# 2022-4T-MNT-1.net
KiCad netlist of a schematic drawn in EasyEDA Pro
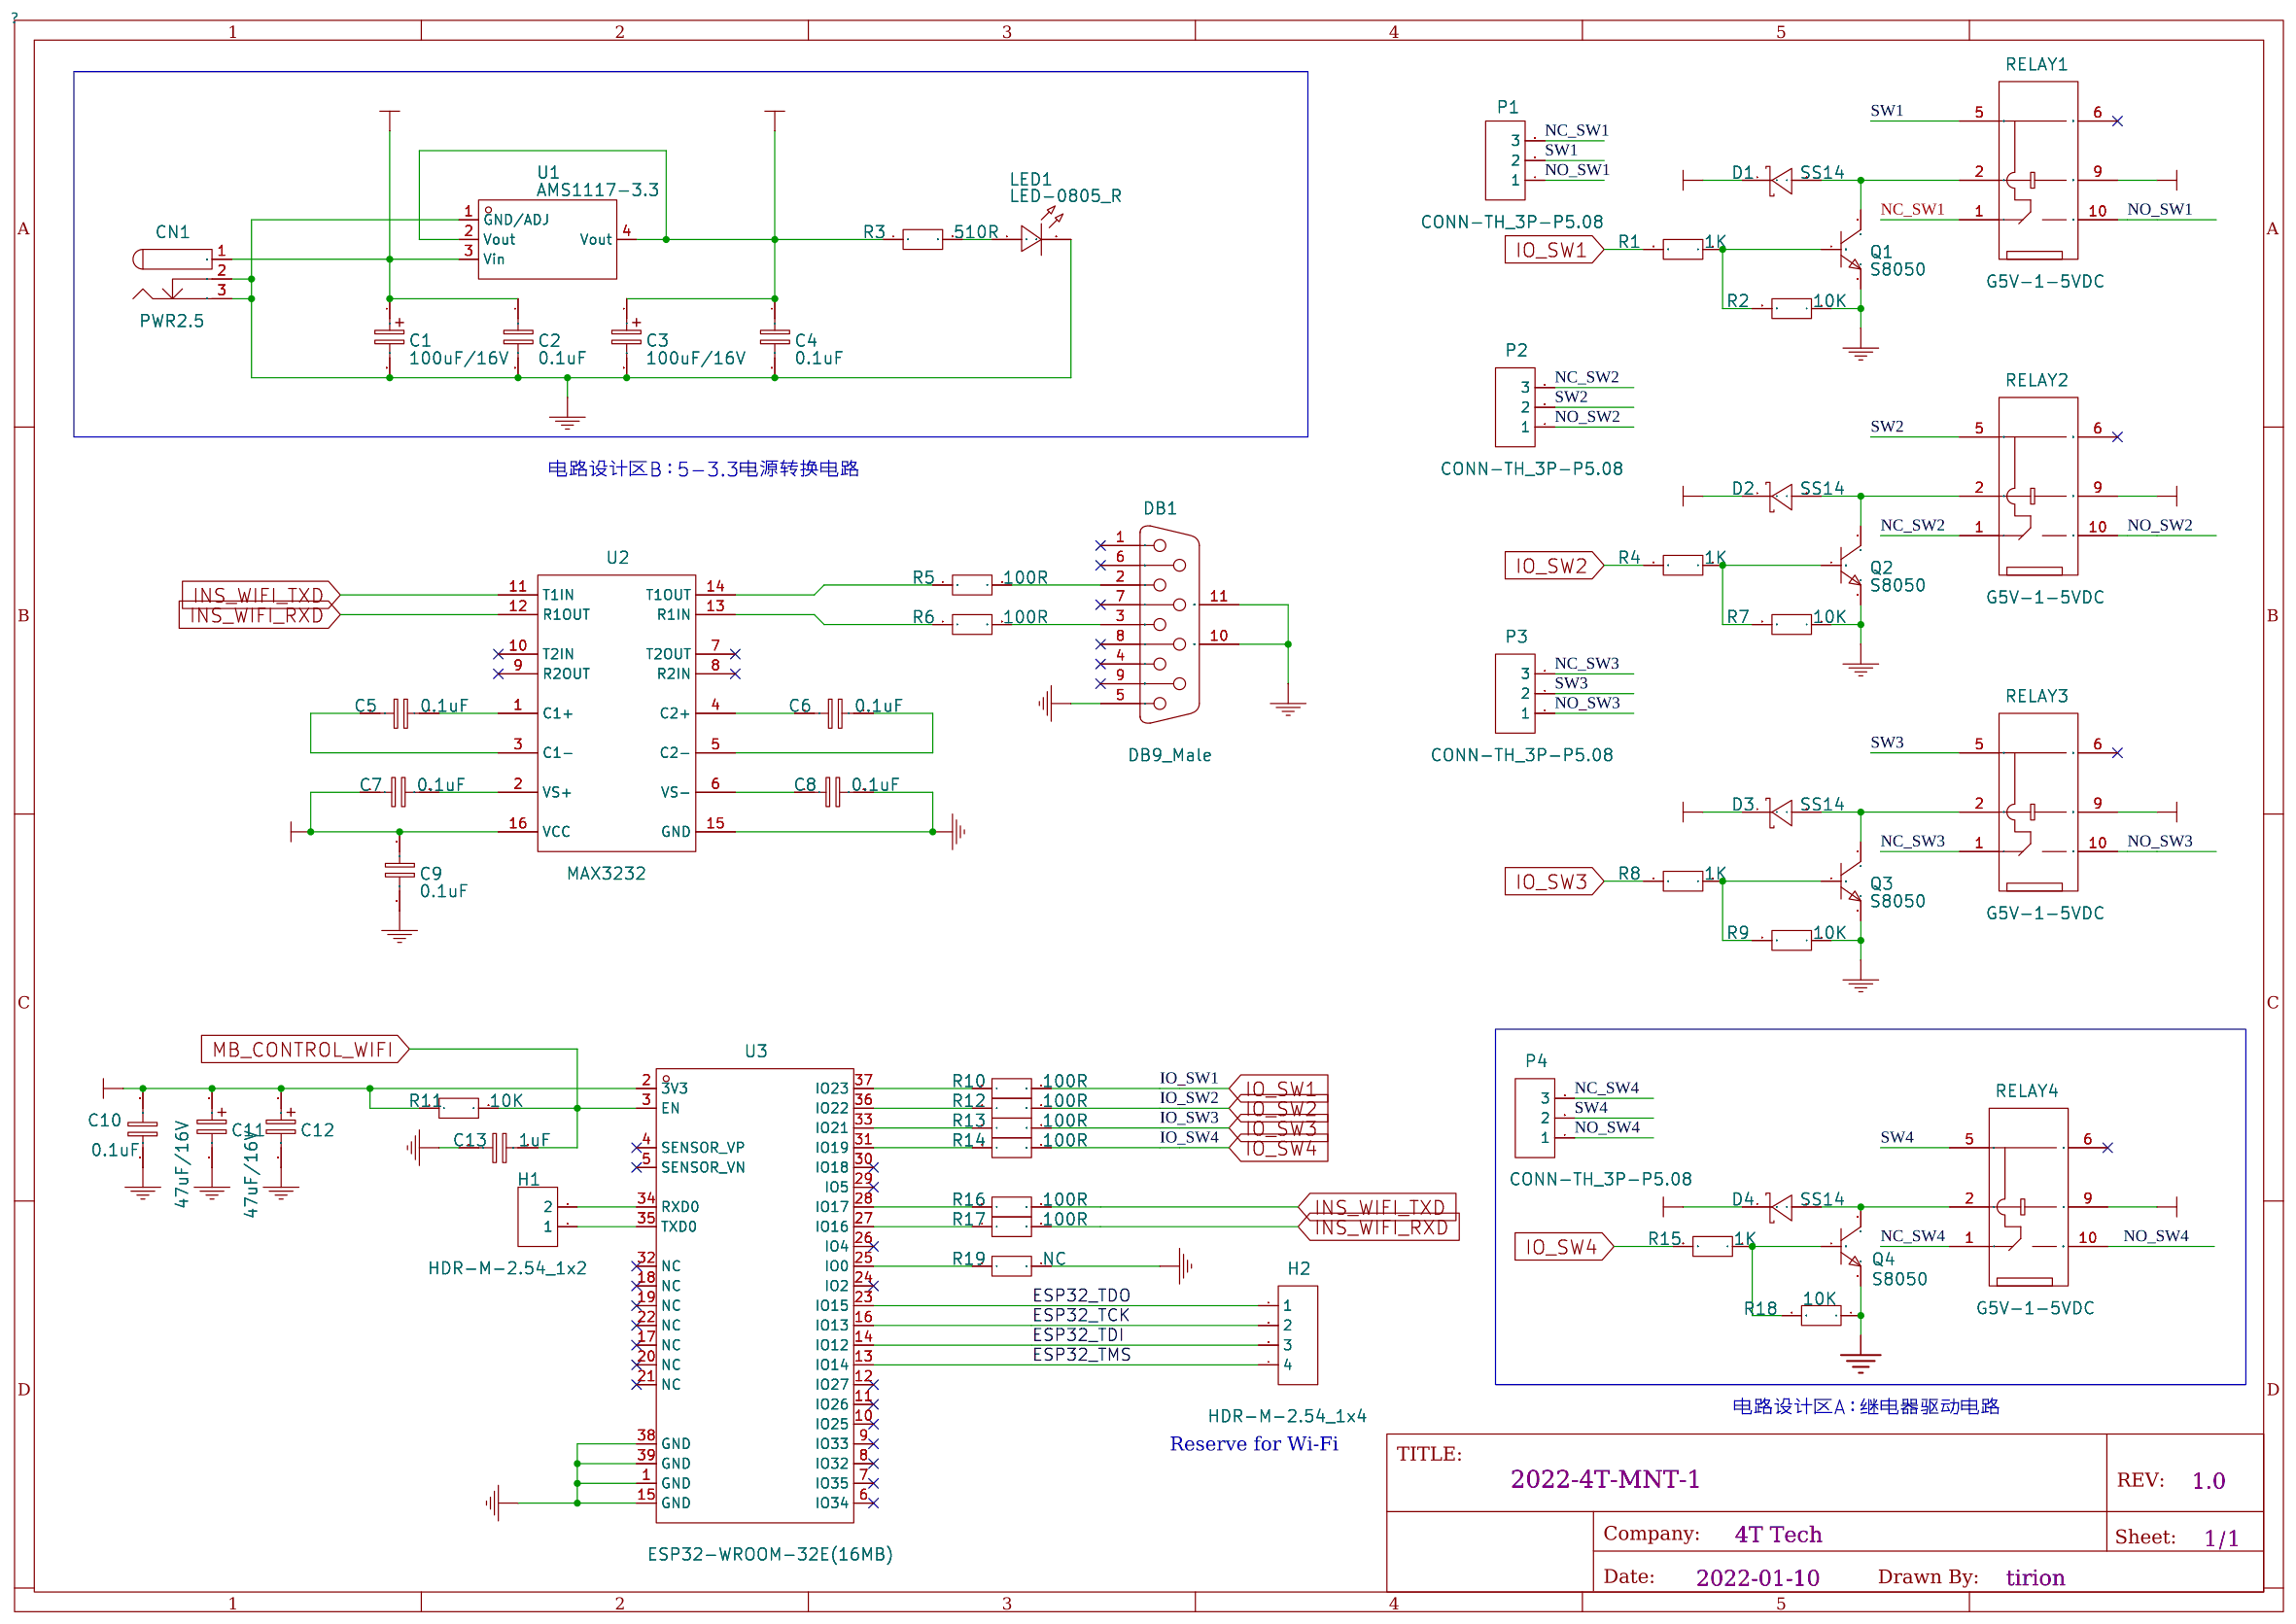
[diagram p0: schematic sheet]

(export (version "E")
  (design (tool "Eeschema 10.0.6"))
  (components
    (comp (ref "C1") (value "100uF/16V") (libsource (lib "easyedapro") (part "100uF/16V")))
    (comp (ref "C2") (value "0.1uF") (libsource (lib "easyedapro") (part "0.1uF")))
    (comp (ref "C3") (value "100uF/16V") (libsource (lib "easyedapro") (part "100uF/16V")))
    (comp (ref "C4") (value "0.1uF") (libsource (lib "easyedapro") (part "0.1uF")))
    (comp (ref "C5") (value "0.1uF") (libsource (lib "easyedapro") (part "0.1uF")))
    (comp (ref "C6") (value "0.1uF") (libsource (lib "easyedapro") (part "0.1uF")))
    (comp (ref "C7") (value "0.1uF") (libsource (lib "easyedapro") (part "0.1uF")))
    (comp (ref "C8") (value "0.1uF") (libsource (lib "easyedapro") (part "0.1uF")))
    (comp (ref "C9") (value "0.1uF") (libsource (lib "easyedapro") (part "0.1uF")))
    (comp (ref "C10") (value "0.1uF") (libsource (lib "easyedapro") (part "0.1uF")))
    (comp (ref "C11") (value "47uF/16V") (libsource (lib "easyedapro") (part "47uF/16V")))
    (comp (ref "C12") (value "47uF/16V") (libsource (lib "easyedapro") (part "47uF/16V")))
    (comp (ref "C13") (value "1uF") (libsource (lib "easyedapro") (part "1uF")))
    (comp (ref "CN1") (value "PWR2.5") (libsource (lib "easyedapro") (part "PWR2.5")))
    (comp (ref "D1")
      (value "SS14")
      (fields (field (name "Manufacturer") "MDD"))
      (libsource (lib "easyedapro") (part "SS14"))
    )
    (comp (ref "D2")
      (value "SS14")
      (fields (field (name "Manufacturer") "MDD"))
      (libsource (lib "easyedapro") (part "SS14"))
    )
    (comp (ref "D3")
      (value "SS14")
      (fields (field (name "Manufacturer") "MDD"))
      (libsource (lib "easyedapro") (part "SS14"))
    )
    (comp (ref "D4")
      (value "SS14")
      (fields (field (name "Manufacturer") "MDD"))
      (libsource (lib "easyedapro") (part "SS14"))
    )
    (comp (ref "DB1")
      (value "DB9_Male")
      (fields (field (name "Manufacturer") "Amphenol"))
      (libsource (lib "easyedapro") (part "DB9_Male"))
    )
    (comp (ref "H1") (value "HDR-M-2.54_1x2") (libsource (lib "easyedapro") (part "HDR-M-2.54_1x2")))
    (comp (ref "H2") (value "HDR-M-2.54_1x4") (libsource (lib "easyedapro") (part "HDR-M-2.54_1x4")))
    (comp (ref "LED1")
      (value "LED-0805_R")
      (fields
        (field (name "Manufacturer Part") "17-21SURC/S530-A3/TR8")
        (field (name "Manufacturer") "EVERLIGHT(台湾亿光)")
      )
      (libsource (lib "easyedapro") (part "LED-0805_R"))
    )
    (comp (ref "P1") (value "CONN-TH_3P-P5.08") (libsource (lib "easyedapro") (part "CONN-TH_3P-P5.08")))
    (comp (ref "P2") (value "CONN-TH_3P-P5.08") (libsource (lib "easyedapro") (part "CONN-TH_3P-P5.08")))
    (comp (ref "P3") (value "CONN-TH_3P-P5.08") (libsource (lib "easyedapro") (part "CONN-TH_3P-P5.08")))
    (comp (ref "P4") (value "CONN-TH_3P-P5.08") (libsource (lib "easyedapro") (part "CONN-TH_3P-P5.08")))
    (comp (ref "Q1")
      (value "S8050")
      (fields (field (name "Manufacturer") "JSMSEMI"))
      (libsource (lib "easyedapro") (part "S8050"))
    )
    (comp (ref "Q2")
      (value "S8050")
      (fields (field (name "Manufacturer") "JSMSEMI"))
      (libsource (lib "easyedapro") (part "S8050"))
    )
    (comp (ref "Q3")
      (value "S8050")
      (fields (field (name "Manufacturer") "JSMSEMI"))
      (libsource (lib "easyedapro") (part "S8050"))
    )
    (comp (ref "Q4")
      (value "S8050")
      (fields (field (name "Manufacturer") "JSMSEMI"))
      (libsource (lib "easyedapro") (part "S8050"))
    )
    (comp (ref "R1") (value "1K") (libsource (lib "easyedapro") (part "1K")))
    (comp (ref "R2") (value "10K") (libsource (lib "easyedapro") (part "10K")))
    (comp (ref "R3") (value "510R") (libsource (lib "easyedapro") (part "510R")))
    (comp (ref "R4") (value "1K") (libsource (lib "easyedapro") (part "1K")))
    (comp (ref "R5") (value "100R") (libsource (lib "easyedapro") (part "100R")))
    (comp (ref "R6") (value "100R") (libsource (lib "easyedapro") (part "100R")))
    (comp (ref "R7") (value "10K") (libsource (lib "easyedapro") (part "10K")))
    (comp (ref "R8") (value "1K") (libsource (lib "easyedapro") (part "1K")))
    (comp (ref "R9") (value "10K") (libsource (lib "easyedapro") (part "10K")))
    (comp (ref "R10") (value "100R") (libsource (lib "easyedapro") (part "100R")))
    (comp (ref "R11") (value "10K") (libsource (lib "easyedapro") (part "10K")))
    (comp (ref "R12") (value "100R") (libsource (lib "easyedapro") (part "100R")))
    (comp (ref "R13") (value "100R") (libsource (lib "easyedapro") (part "100R")))
    (comp (ref "R14") (value "100R") (libsource (lib "easyedapro") (part "100R")))
    (comp (ref "R15") (value "1K") (libsource (lib "easyedapro") (part "1K")))
    (comp (ref "R16") (value "100R") (libsource (lib "easyedapro") (part "100R")))
    (comp (ref "R17") (value "100R") (libsource (lib "easyedapro") (part "100R")))
    (comp (ref "R18") (value "10K") (libsource (lib "easyedapro") (part "10K")))
    (comp (ref "R19") (value "NC") (libsource (lib "easyedapro") (part "NC")))
    (comp (ref "RELAY1")
      (value "G5V-1-5VDC")
      (fields (field (name "Manufacturer") "OMRON"))
      (libsource (lib "easyedapro") (part "G5V-1-5VDC"))
    )
    (comp (ref "RELAY2")
      (value "G5V-1-5VDC")
      (fields (field (name "Manufacturer") "OMRON"))
      (libsource (lib "easyedapro") (part "G5V-1-5VDC"))
    )
    (comp (ref "RELAY3")
      (value "G5V-1-5VDC")
      (fields (field (name "Manufacturer") "OMRON"))
      (libsource (lib "easyedapro") (part "G5V-1-5VDC"))
    )
    (comp (ref "RELAY4")
      (value "G5V-1-5VDC")
      (fields (field (name "Manufacturer") "OMRON"))
      (libsource (lib "easyedapro") (part "G5V-1-5VDC"))
    )
    (comp (ref "U1")
      (value "AMS1117-3.3")
      (fields (field (name "Manufacturer") "AMS"))
      (libsource (lib "easyedapro") (part "AMS1117-3.3"))
    )
    (comp (ref "U2")
      (value "MAX3232")
      (fields (field (name "Manufacturer") "TI"))
      (libsource (lib "easyedapro") (part "MAX3232"))
    )
    (comp (ref "U3")
      (value "ESP32-WROOM-32E(16MB)")
      (fields (field (name "Manufacturer") "Espressif Systems"))
      (libsource (lib "easyedapro") (part "ESP32-WROOM-32E(16MB)"))
    )
  )
  (nets
    (net (code "1") (name "+3V3") (class "Default")
      (node (ref "C10") (pin "2") (pinfunction "2_2") (pintype "input"))
      (node (ref "C11") (pin "1") (pinfunction "1_1") (pintype "input"))
      (node (ref "C12") (pin "1") (pinfunction "1_1") (pintype "input"))
      (node (ref "C3") (pin "1") (pinfunction "1_1") (pintype "input"))
      (node (ref "C4") (pin "1") (pinfunction "1_1") (pintype "input"))
      (node (ref "C7") (pin "1") (pinfunction "1_1") (pintype "input"))
      (node (ref "C9") (pin "1") (pinfunction "1_1") (pintype "input"))
      (node (ref "R11") (pin "1") (pinfunction "1_1") (pintype "input"))
      (node (ref "R3") (pin "1") (pinfunction "1_1") (pintype "input"))
      (node (ref "U1") (pin "2") (pinfunction "Vout_2") (pintype "input"))
      (node (ref "U1") (pin "4") (pinfunction "Vout_4") (pintype "input"))
      (node (ref "U2") (pin "16") (pinfunction "VCC_16") (pintype "input"))
      (node (ref "U3") (pin "2") (pinfunction "3V3_2") (pintype "input"))
    )
    (net (code "2") (name "+5V") (class "Default")
      (node (ref "C1") (pin "1") (pinfunction "1_1") (pintype "input"))
      (node (ref "C2") (pin "1") (pinfunction "1_1") (pintype "input"))
      (node (ref "CN1") (pin "1") (pinfunction "ADJ_1") (pintype "input"))
      (node (ref "D1") (pin "1") (pinfunction "K_1") (pintype "input"))
      (node (ref "D2") (pin "1") (pinfunction "K_1") (pintype "input"))
      (node (ref "D3") (pin "1") (pinfunction "K_1") (pintype "input"))
      (node (ref "D4") (pin "1") (pinfunction "K_1") (pintype "input"))
      (node (ref "RELAY1") (pin "9") (pinfunction "9_9") (pintype "input"))
      (node (ref "RELAY2") (pin "9") (pinfunction "9_9") (pintype "input"))
      (node (ref "RELAY3") (pin "9") (pinfunction "9_9") (pintype "input"))
      (node (ref "RELAY4") (pin "9") (pinfunction "9_9") (pintype "input"))
      (node (ref "U1") (pin "3") (pinfunction "Vin_3") (pintype "input"))
    )
    (net (code "3") (name "/ESP32_TCK") (class "Default")
      (node (ref "H2") (pin "2") (pinfunction "2_2") (pintype "input"))
      (node (ref "U3") (pin "16") (pinfunction "IO13_16") (pintype "input"))
    )
    (net (code "4") (name "/ESP32_TDI") (class "Default")
      (node (ref "H2") (pin "3") (pinfunction "3_3") (pintype "input"))
      (node (ref "U3") (pin "14") (pinfunction "IO12_14") (pintype "input"))
    )
    (net (code "5") (name "/ESP32_TDO") (class "Default")
      (node (ref "H2") (pin "1") (pinfunction "1_1") (pintype "input"))
      (node (ref "U3") (pin "23") (pinfunction "IO15_23") (pintype "input"))
    )
    (net (code "6") (name "/ESP32_TMS") (class "Default")
      (node (ref "H2") (pin "4") (pinfunction "4_4") (pintype "input"))
      (node (ref "U3") (pin "13") (pinfunction "IO14_13") (pintype "input"))
    )
    (net (code "7") (name "/NC_SW1") (class "Default")
      (node (ref "P1") (pin "3") (pinfunction "3_3") (pintype "input"))
      (node (ref "RELAY1") (pin "1") (pinfunction "1_1") (pintype "input"))
    )
    (net (code "8") (name "/NC_SW2") (class "Default")
      (node (ref "P2") (pin "3") (pinfunction "3_3") (pintype "input"))
      (node (ref "RELAY2") (pin "1") (pinfunction "1_1") (pintype "input"))
    )
    (net (code "9") (name "/NC_SW3") (class "Default")
      (node (ref "P3") (pin "3") (pinfunction "3_3") (pintype "input"))
      (node (ref "RELAY3") (pin "1") (pinfunction "1_1") (pintype "input"))
    )
    (net (code "10") (name "/NC_SW4") (class "Default")
      (node (ref "P4") (pin "3") (pinfunction "3_3") (pintype "input"))
      (node (ref "RELAY4") (pin "1") (pinfunction "1_1") (pintype "input"))
    )
    (net (code "11") (name "/NO_SW1") (class "Default")
      (node (ref "P1") (pin "1") (pinfunction "1_1") (pintype "input"))
      (node (ref "RELAY1") (pin "10") (pinfunction "10_10") (pintype "input"))
    )
    (net (code "12") (name "/NO_SW2") (class "Default")
      (node (ref "P2") (pin "1") (pinfunction "1_1") (pintype "input"))
      (node (ref "RELAY2") (pin "10") (pinfunction "10_10") (pintype "input"))
    )
    (net (code "13") (name "/NO_SW3") (class "Default")
      (node (ref "P3") (pin "1") (pinfunction "1_1") (pintype "input"))
      (node (ref "RELAY3") (pin "10") (pinfunction "10_10") (pintype "input"))
    )
    (net (code "14") (name "/NO_SW4") (class "Default")
      (node (ref "P4") (pin "1") (pinfunction "1_1") (pintype "input"))
      (node (ref "RELAY4") (pin "10") (pinfunction "10_10") (pintype "input"))
    )
    (net (code "15") (name "/SW1") (class "Default")
      (node (ref "P1") (pin "2") (pinfunction "2_2") (pintype "input"))
      (node (ref "RELAY1") (pin "5") (pinfunction "5_5") (pintype "input"))
    )
    (net (code "16") (name "/SW2") (class "Default")
      (node (ref "P2") (pin "2") (pinfunction "2_2") (pintype "input"))
      (node (ref "RELAY2") (pin "5") (pinfunction "5_5") (pintype "input"))
    )
    (net (code "17") (name "/SW3") (class "Default")
      (node (ref "P3") (pin "2") (pinfunction "2_2") (pintype "input"))
      (node (ref "RELAY3") (pin "5") (pinfunction "5_5") (pintype "input"))
    )
    (net (code "18") (name "/SW4") (class "Default")
      (node (ref "P4") (pin "2") (pinfunction "2_2") (pintype "input"))
      (node (ref "RELAY4") (pin "5") (pinfunction "5_5") (pintype "input"))
    )
    (net (code "19") (name "GND") (class "Default")
      (node (ref "C1") (pin "2") (pinfunction "2_2") (pintype "input"))
      (node (ref "C10") (pin "1") (pinfunction "1_1") (pintype "input"))
      (node (ref "C11") (pin "2") (pinfunction "2_2") (pintype "input"))
      (node (ref "C12") (pin "2") (pinfunction "2_2") (pintype "input"))
      (node (ref "C13") (pin "2") (pinfunction "2_2") (pintype "input"))
      (node (ref "C2") (pin "2") (pinfunction "2_2") (pintype "input"))
      (node (ref "C3") (pin "2") (pinfunction "2_2") (pintype "input"))
      (node (ref "C4") (pin "2") (pinfunction "2_2") (pintype "input"))
      (node (ref "C8") (pin "2") (pinfunction "2_2") (pintype "input"))
      (node (ref "C9") (pin "2") (pinfunction "2_2") (pintype "input"))
      (node (ref "CN1") (pin "2") (pinfunction "ADJ_2") (pintype "input"))
      (node (ref "CN1") (pin "3") (pinfunction "ADJ_3") (pintype "input"))
      (node (ref "DB1") (pin "10") (pinfunction "MH1_10") (pintype "input"))
      (node (ref "DB1") (pin "11") (pinfunction "MH2_11") (pintype "input"))
      (node (ref "DB1") (pin "5") (pinfunction "5_5") (pintype "input"))
      (node (ref "LED1") (pin "2") (pinfunction "2_2") (pintype "input"))
      (node (ref "Q1") (pin "2") (pinfunction "E_2") (pintype "input"))
      (node (ref "Q2") (pin "2") (pinfunction "E_2") (pintype "input"))
      (node (ref "Q3") (pin "2") (pinfunction "E_2") (pintype "input"))
      (node (ref "Q4") (pin "2") (pinfunction "E_2") (pintype "input"))
      (node (ref "R18") (pin "1") (pinfunction "1_1") (pintype "input"))
      (node (ref "R19") (pin "2") (pinfunction "2_2") (pintype "input"))
      (node (ref "R2") (pin "1") (pinfunction "1_1") (pintype "input"))
      (node (ref "R7") (pin "1") (pinfunction "1_1") (pintype "input"))
      (node (ref "R9") (pin "1") (pinfunction "1_1") (pintype "input"))
      (node (ref "U1") (pin "1") (pinfunction "GND/ADJ_1") (pintype "input"))
      (node (ref "U2") (pin "15") (pinfunction "GND_15") (pintype "input"))
      (node (ref "U3") (pin "1") (pinfunction "GND_1") (pintype "input"))
      (node (ref "U3") (pin "15") (pinfunction "GND_15") (pintype "input"))
      (node (ref "U3") (pin "38") (pinfunction "GND_38") (pintype "input"))
      (node (ref "U3") (pin "39") (pinfunction "GND_39") (pintype "input"))
    )
    (net (code "20") (name "INS_WIFI_RXD") (class "Default")
      (node (ref "R17") (pin "2") (pinfunction "2_2") (pintype "input"))
      (node (ref "U2") (pin "12") (pinfunction "R1OUT_12") (pintype "output"))
    )
    (net (code "21") (name "INS_WIFI_TXD") (class "Default")
      (node (ref "R16") (pin "2") (pinfunction "2_2") (pintype "input"))
      (node (ref "U2") (pin "11") (pinfunction "T1IN_11") (pintype "input"))
    )
    (net (code "22") (name "IO_SW1") (class "Default")
      (node (ref "R1") (pin "2") (pinfunction "2_2") (pintype "input"))
      (node (ref "R10") (pin "2") (pinfunction "2_2") (pintype "input"))
    )
    (net (code "23") (name "IO_SW2") (class "Default")
      (node (ref "R12") (pin "2") (pinfunction "2_2") (pintype "input"))
      (node (ref "R4") (pin "2") (pinfunction "2_2") (pintype "input"))
    )
    (net (code "24") (name "IO_SW3") (class "Default")
      (node (ref "R13") (pin "2") (pinfunction "2_2") (pintype "input"))
      (node (ref "R8") (pin "2") (pinfunction "2_2") (pintype "input"))
    )
    (net (code "25") (name "IO_SW4") (class "Default")
      (node (ref "R14") (pin "2") (pinfunction "2_2") (pintype "input"))
      (node (ref "R15") (pin "2") (pinfunction "2_2") (pintype "input"))
    )
    (net (code "26") (name "MB_CONTROL_WIFI") (class "Default")
      (node (ref "C13") (pin "1") (pinfunction "1_1") (pintype "input"))
      (node (ref "R11") (pin "2") (pinfunction "2_2") (pintype "input"))
      (node (ref "U3") (pin "3") (pinfunction "EN_3") (pintype "input"))
    )
    (net (code "27") (name "Net-(D1-A)") (class "Default")
      (node (ref "D1") (pin "2") (pinfunction "A_2") (pintype "input"))
      (node (ref "Q1") (pin "3") (pinfunction "C_3") (pintype "input"))
      (node (ref "RELAY1") (pin "2") (pinfunction "2_2") (pintype "input"))
    )
    (net (code "28") (name "Net-(D2-A)") (class "Default")
      (node (ref "D2") (pin "2") (pinfunction "A_2") (pintype "input"))
      (node (ref "Q2") (pin "3") (pinfunction "C_3") (pintype "input"))
      (node (ref "RELAY2") (pin "2") (pinfunction "2_2") (pintype "input"))
    )
    (net (code "29") (name "Net-(D3-A)") (class "Default")
      (node (ref "D3") (pin "2") (pinfunction "A_2") (pintype "input"))
      (node (ref "Q3") (pin "3") (pinfunction "C_3") (pintype "input"))
      (node (ref "RELAY3") (pin "2") (pinfunction "2_2") (pintype "input"))
    )
    (net (code "30") (name "Net-(D4-A)") (class "Default")
      (node (ref "D4") (pin "2") (pinfunction "A_2") (pintype "input"))
      (node (ref "Q4") (pin "3") (pinfunction "C_3") (pintype "input"))
      (node (ref "RELAY4") (pin "2") (pinfunction "2_2") (pintype "input"))
    )
    (net (code "31") (name "Net-(DB1-Pad2)") (class "Default")
      (node (ref "DB1") (pin "2") (pinfunction "2_2") (pintype "input"))
      (node (ref "R5") (pin "2") (pinfunction "2_2") (pintype "input"))
    )
    (net (code "32") (name "Net-(DB1-Pad3)") (class "Default")
      (node (ref "DB1") (pin "3") (pinfunction "3_3") (pintype "input"))
      (node (ref "R6") (pin "2") (pinfunction "2_2") (pintype "input"))
    )
    (net (code "33") (name "Net-(LED1-Pad1)") (class "Default")
      (node (ref "LED1") (pin "1") (pinfunction "1_1") (pintype "input"))
      (node (ref "R3") (pin "2") (pinfunction "2_2") (pintype "input"))
    )
    (net (code "34") (name "Net-(Q1-B)") (class "Default")
      (node (ref "Q1") (pin "1") (pinfunction "B_1") (pintype "input"))
      (node (ref "R1") (pin "1") (pinfunction "1_1") (pintype "input"))
      (node (ref "R2") (pin "2") (pinfunction "2_2") (pintype "input"))
    )
    (net (code "35") (name "Net-(Q2-B)") (class "Default")
      (node (ref "Q2") (pin "1") (pinfunction "B_1") (pintype "input"))
      (node (ref "R4") (pin "1") (pinfunction "1_1") (pintype "input"))
      (node (ref "R7") (pin "2") (pinfunction "2_2") (pintype "input"))
    )
    (net (code "36") (name "Net-(Q3-B)") (class "Default")
      (node (ref "Q3") (pin "1") (pinfunction "B_1") (pintype "input"))
      (node (ref "R8") (pin "1") (pinfunction "1_1") (pintype "input"))
      (node (ref "R9") (pin "2") (pinfunction "2_2") (pintype "input"))
    )
    (net (code "37") (name "Net-(Q4-B)") (class "Default")
      (node (ref "Q4") (pin "1") (pinfunction "B_1") (pintype "input"))
      (node (ref "R15") (pin "1") (pinfunction "1_1") (pintype "input"))
      (node (ref "R18") (pin "2") (pinfunction "2_2") (pintype "input"))
    )
    (net (code "38") (name "Net-(U2-C1+)") (class "Default")
      (node (ref "C5") (pin "1") (pinfunction "1_1") (pintype "input"))
      (node (ref "U2") (pin "1") (pinfunction "C1+_1") (pintype "input"))
    )
    (net (code "39") (name "Net-(U2-C1-)") (class "Default")
      (node (ref "C5") (pin "2") (pinfunction "2_2") (pintype "input"))
      (node (ref "U2") (pin "3") (pinfunction "C1-_3") (pintype "input"))
    )
    (net (code "40") (name "Net-(U2-C2+)") (class "Default")
      (node (ref "C6") (pin "2") (pinfunction "2_2") (pintype "input"))
      (node (ref "U2") (pin "4") (pinfunction "C2+_4") (pintype "input"))
    )
    (net (code "41") (name "Net-(U2-C2-)") (class "Default")
      (node (ref "C6") (pin "1") (pinfunction "1_1") (pintype "input"))
      (node (ref "U2") (pin "5") (pinfunction "C2-_5") (pintype "input"))
    )
    (net (code "42") (name "Net-(U2-R1IN)") (class "Default")
      (node (ref "R6") (pin "1") (pinfunction "1_1") (pintype "input"))
      (node (ref "U2") (pin "13") (pinfunction "R1IN_13") (pintype "input"))
    )
    (net (code "43") (name "Net-(U2-T1OUT)") (class "Default")
      (node (ref "R5") (pin "1") (pinfunction "1_1") (pintype "input"))
      (node (ref "U2") (pin "14") (pinfunction "T1OUT_14") (pintype "output"))
    )
    (net (code "44") (name "Net-(U2-VS+)") (class "Default")
      (node (ref "C7") (pin "2") (pinfunction "2_2") (pintype "input"))
      (node (ref "U2") (pin "2") (pinfunction "VS+_2") (pintype "input"))
    )
    (net (code "45") (name "Net-(U2-VS-)") (class "Default")
      (node (ref "C8") (pin "1") (pinfunction "1_1") (pintype "input"))
      (node (ref "U2") (pin "6") (pinfunction "VS-_6") (pintype "input"))
    )
    (net (code "46") (name "Net-(U3-IO0)") (class "Default")
      (node (ref "R19") (pin "1") (pinfunction "1_1") (pintype "input"))
      (node (ref "U3") (pin "25") (pinfunction "IO0_25") (pintype "input"))
    )
    (net (code "47") (name "Net-(U3-IO16)") (class "Default")
      (node (ref "R17") (pin "1") (pinfunction "1_1") (pintype "input"))
      (node (ref "U3") (pin "27") (pinfunction "IO16_27") (pintype "input"))
    )
    (net (code "48") (name "Net-(U3-IO17)") (class "Default")
      (node (ref "R16") (pin "1") (pinfunction "1_1") (pintype "input"))
      (node (ref "U3") (pin "28") (pinfunction "IO17_28") (pintype "input"))
    )
    (net (code "49") (name "Net-(U3-IO19)") (class "Default")
      (node (ref "R14") (pin "1") (pinfunction "1_1") (pintype "input"))
      (node (ref "U3") (pin "31") (pinfunction "IO19_31") (pintype "input"))
    )
    (net (code "50") (name "Net-(U3-IO21)") (class "Default")
      (node (ref "R13") (pin "1") (pinfunction "1_1") (pintype "input"))
      (node (ref "U3") (pin "33") (pinfunction "IO21_33") (pintype "input"))
    )
    (net (code "51") (name "Net-(U3-IO22)") (class "Default")
      (node (ref "R12") (pin "1") (pinfunction "1_1") (pintype "input"))
      (node (ref "U3") (pin "36") (pinfunction "IO22_36") (pintype "input"))
    )
    (net (code "52") (name "Net-(U3-IO23)") (class "Default")
      (node (ref "R10") (pin "1") (pinfunction "1_1") (pintype "input"))
      (node (ref "U3") (pin "37") (pinfunction "IO23_37") (pintype "input"))
    )
    (net (code "53") (name "Net-(U3-RXD0)") (class "Default")
      (node (ref "H1") (pin "2") (pinfunction "2_2") (pintype "input"))
      (node (ref "U3") (pin "34") (pinfunction "RXD0_34") (pintype "input"))
    )
    (net (code "54") (name "Net-(U3-TXD0)") (class "Default")
      (node (ref "H1") (pin "1") (pinfunction "1_1") (pintype "input"))
      (node (ref "U3") (pin "35") (pinfunction "TXD0_35") (pintype "input"))
    )
    (net (code "55") (name "unconnected-(DB1-Pad1)") (class "Default")
      (node (ref "DB1") (pin "1") (pinfunction "1_1") (pintype "input+no_connect"))
    )
    (net (code "56") (name "unconnected-(DB1-Pad4)") (class "Default")
      (node (ref "DB1") (pin "4") (pinfunction "4_4") (pintype "input+no_connect"))
    )
    (net (code "57") (name "unconnected-(DB1-Pad6)") (class "Default")
      (node (ref "DB1") (pin "6") (pinfunction "6_6") (pintype "input+no_connect"))
    )
    (net (code "58") (name "unconnected-(DB1-Pad7)") (class "Default")
      (node (ref "DB1") (pin "7") (pinfunction "7_7") (pintype "input+no_connect"))
    )
    (net (code "59") (name "unconnected-(DB1-Pad8)") (class "Default")
      (node (ref "DB1") (pin "8") (pinfunction "8_8") (pintype "input+no_connect"))
    )
    (net (code "60") (name "unconnected-(DB1-Pad9)") (class "Default")
      (node (ref "DB1") (pin "9") (pinfunction "9_9") (pintype "input+no_connect"))
    )
    (net (code "61") (name "unconnected-(RELAY1-Pad6)") (class "Default")
      (node (ref "RELAY1") (pin "6") (pinfunction "6_6") (pintype "input+no_connect"))
    )
    (net (code "62") (name "unconnected-(RELAY2-Pad6)") (class "Default")
      (node (ref "RELAY2") (pin "6") (pinfunction "6_6") (pintype "input+no_connect"))
    )
    (net (code "63") (name "unconnected-(RELAY3-Pad6)") (class "Default")
      (node (ref "RELAY3") (pin "6") (pinfunction "6_6") (pintype "input+no_connect"))
    )
    (net (code "64") (name "unconnected-(RELAY4-Pad6)") (class "Default")
      (node (ref "RELAY4") (pin "6") (pinfunction "6_6") (pintype "input+no_connect"))
    )
    (net (code "65") (name "unconnected-(U2-R2IN-Pad8)") (class "Default")
      (node (ref "U2") (pin "8") (pinfunction "R2IN_8") (pintype "input+no_connect"))
    )
    (net (code "66") (name "unconnected-(U2-R2OUT-Pad9)") (class "Default")
      (node (ref "U2") (pin "9") (pinfunction "R2OUT_9") (pintype "output+no_connect"))
    )
    (net (code "67") (name "unconnected-(U2-T2IN-Pad10)") (class "Default")
      (node (ref "U2") (pin "10") (pinfunction "T2IN_10") (pintype "input+no_connect"))
    )
    (net (code "68") (name "unconnected-(U2-T2OUT-Pad7)") (class "Default")
      (node (ref "U2") (pin "7") (pinfunction "T2OUT_7") (pintype "output+no_connect"))
    )
    (net (code "69") (name "unconnected-(U3-IO2-Pad24)") (class "Default")
      (node (ref "U3") (pin "24") (pinfunction "IO2_24") (pintype "input+no_connect"))
    )
    (net (code "70") (name "unconnected-(U3-IO4-Pad26)") (class "Default")
      (node (ref "U3") (pin "26") (pinfunction "IO4_26") (pintype "input+no_connect"))
    )
    (net (code "71") (name "unconnected-(U3-IO5-Pad29)") (class "Default")
      (node (ref "U3") (pin "29") (pinfunction "IO5_29") (pintype "input+no_connect"))
    )
    (net (code "72") (name "unconnected-(U3-IO18-Pad30)") (class "Default")
      (node (ref "U3") (pin "30") (pinfunction "IO18_30") (pintype "input+no_connect"))
    )
    (net (code "73") (name "unconnected-(U3-IO25-Pad10)") (class "Default")
      (node (ref "U3") (pin "10") (pinfunction "IO25_10") (pintype "input+no_connect"))
    )
    (net (code "74") (name "unconnected-(U3-IO26-Pad11)") (class "Default")
      (node (ref "U3") (pin "11") (pinfunction "IO26_11") (pintype "input+no_connect"))
    )
    (net (code "75") (name "unconnected-(U3-IO27-Pad12)") (class "Default")
      (node (ref "U3") (pin "12") (pinfunction "IO27_12") (pintype "input+no_connect"))
    )
    (net (code "76") (name "unconnected-(U3-IO32-Pad8)") (class "Default")
      (node (ref "U3") (pin "8") (pinfunction "IO32_8") (pintype "input+no_connect"))
    )
    (net (code "77") (name "unconnected-(U3-IO33-Pad9)") (class "Default")
      (node (ref "U3") (pin "9") (pinfunction "IO33_9") (pintype "input+no_connect"))
    )
    (net (code "78") (name "unconnected-(U3-IO34-Pad6)") (class "Default")
      (node (ref "U3") (pin "6") (pinfunction "IO34_6") (pintype "input+no_connect"))
    )
    (net (code "79") (name "unconnected-(U3-IO35-Pad7)") (class "Default")
      (node (ref "U3") (pin "7") (pinfunction "IO35_7") (pintype "input+no_connect"))
    )
    (net (code "80") (name "unconnected-(U3-NC-Pad17)") (class "Default")
      (node (ref "U3") (pin "17") (pinfunction "NC_17") (pintype "input+no_connect"))
    )
    (net (code "81") (name "unconnected-(U3-NC-Pad18)") (class "Default")
      (node (ref "U3") (pin "18") (pinfunction "NC_18") (pintype "input+no_connect"))
    )
    (net (code "82") (name "unconnected-(U3-NC-Pad19)") (class "Default")
      (node (ref "U3") (pin "19") (pinfunction "NC_19") (pintype "input+no_connect"))
    )
    (net (code "83") (name "unconnected-(U3-NC-Pad20)") (class "Default")
      (node (ref "U3") (pin "20") (pinfunction "NC_20") (pintype "input+no_connect"))
    )
    (net (code "84") (name "unconnected-(U3-NC-Pad21)") (class "Default")
      (node (ref "U3") (pin "21") (pinfunction "NC_21") (pintype "input+no_connect"))
    )
    (net (code "85") (name "unconnected-(U3-NC-Pad22)") (class "Default")
      (node (ref "U3") (pin "22") (pinfunction "NC_22") (pintype "input+no_connect"))
    )
    (net (code "86") (name "unconnected-(U3-NC-Pad32)") (class "Default")
      (node (ref "U3") (pin "32") (pinfunction "NC_32") (pintype "input+no_connect"))
    )
    (net (code "87") (name "unconnected-(U3-SENSOR_VN-Pad5)") (class "Default")
      (node (ref "U3") (pin "5") (pinfunction "SENSOR_VN_5") (pintype "input+no_connect"))
    )
    (net (code "88") (name "unconnected-(U3-SENSOR_VP-Pad4)") (class "Default")
      (node (ref "U3") (pin "4") (pinfunction "SENSOR_VP_4") (pintype "input+no_connect"))
    )
  )
)
